# rangkaian_score_foul.net
KiCad netlist of a schematic drawn in EAGLE
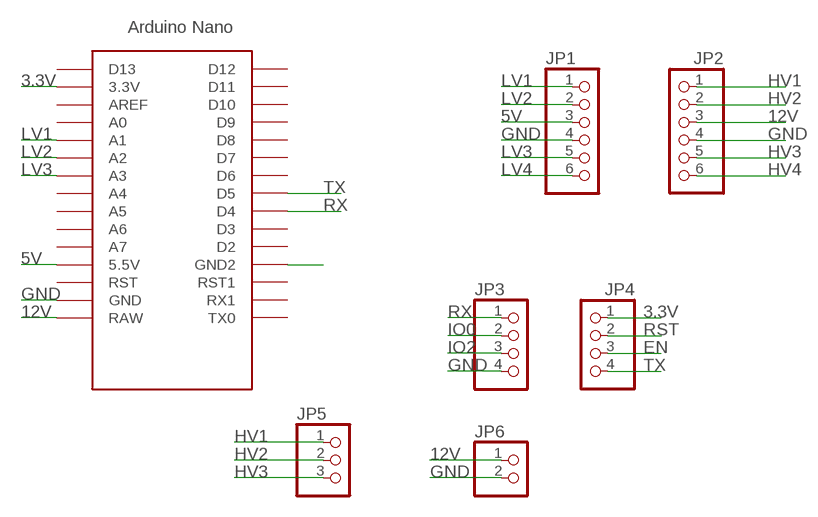
[diagram p0: schematic, sheet 1]

(export (version "E")
  (design (tool "Eeschema 10.0.6"))
  (components
    (comp (ref "JP1")
      (value "PINHD-1X6")
      (footprint "eagle-import:1X06")
      (libsource (lib "eagle-import") (part "PINHD-1X6"))
    )
    (comp (ref "JP2")
      (value "PINHD-1X6")
      (footprint "eagle-import:1X06")
      (libsource (lib "eagle-import") (part "PINHD-1X6"))
    )
    (comp (ref "JP3")
      (value "PINHD-1X4")
      (footprint "eagle-import:1X04")
      (libsource (lib "eagle-import") (part "PINHD-1X4"))
    )
    (comp (ref "JP4")
      (value "PINHD-1X4")
      (footprint "eagle-import:1X04")
      (libsource (lib "eagle-import") (part "PINHD-1X4"))
    )
    (comp (ref "JP5")
      (value "PINHD-1X3")
      (footprint "eagle-import:1X03")
      (libsource (lib "eagle-import") (part "PINHD-1X3"))
    )
    (comp (ref "JP6")
      (value "PINHD-1X2")
      (footprint "eagle-import:1X02")
      (libsource (lib "eagle-import") (part "PINHD-1X2"))
    )
    (comp (ref "U$1")
      (value "NANO")
      (footprint "eagle-import:NANO")
      (libsource (lib "eagle-import") (part "NANO"))
    )
  )
  (nets
    (net (code "1") (name "/3.3V") (class "Default")
      (node (ref "JP4") (pin "1") (pinfunction "1_1") (pintype "passive"))
      (node (ref "U$1") (pin "3.3V") (pinfunction "3.3V_3.3V") (pintype "bidirectional"))
    )
    (net (code "2") (name "/5V") (class "Default")
      (node (ref "JP1") (pin "3") (pinfunction "3_3") (pintype "passive"))
      (node (ref "U$1") (pin "5V") (pinfunction "5.5V_5V") (pintype "bidirectional"))
    )
    (net (code "3") (name "/12V") (class "Default")
      (node (ref "JP2") (pin "3") (pinfunction "3_3") (pintype "passive"))
      (node (ref "JP6") (pin "1") (pinfunction "1_1") (pintype "passive"))
      (node (ref "U$1") (pin "RAW") (pinfunction "RAW_RAW") (pintype "bidirectional"))
    )
    (net (code "4") (name "/EN") (class "Default")
      (node (ref "JP4") (pin "3") (pinfunction "3_3") (pintype "passive"))
    )
    (net (code "5") (name "/GND") (class "Default")
      (node (ref "JP1") (pin "4") (pinfunction "4_4") (pintype "passive"))
      (node (ref "JP2") (pin "4") (pinfunction "4_4") (pintype "passive"))
      (node (ref "JP3") (pin "4") (pinfunction "4_4") (pintype "passive"))
      (node (ref "JP6") (pin "2") (pinfunction "2_2") (pintype "passive"))
      (node (ref "U$1") (pin "GND") (pinfunction "GND_GND") (pintype "bidirectional"))
    )
    (net (code "6") (name "/HV1") (class "Default")
      (node (ref "JP2") (pin "1") (pinfunction "1_1") (pintype "passive"))
      (node (ref "JP5") (pin "1") (pinfunction "1_1") (pintype "passive"))
    )
    (net (code "7") (name "/HV2") (class "Default")
      (node (ref "JP2") (pin "2") (pinfunction "2_2") (pintype "passive"))
      (node (ref "JP5") (pin "2") (pinfunction "2_2") (pintype "passive"))
    )
    (net (code "8") (name "/HV3") (class "Default")
      (node (ref "JP2") (pin "5") (pinfunction "5_5") (pintype "passive"))
      (node (ref "JP5") (pin "3") (pinfunction "3_3") (pintype "passive"))
    )
    (net (code "9") (name "/HV4") (class "Default")
      (node (ref "JP2") (pin "6") (pinfunction "6_6") (pintype "passive"))
    )
    (net (code "10") (name "/IO0") (class "Default")
      (node (ref "JP3") (pin "2") (pinfunction "2_2") (pintype "passive"))
    )
    (net (code "11") (name "/IO2") (class "Default")
      (node (ref "JP3") (pin "3") (pinfunction "3_3") (pintype "passive"))
    )
    (net (code "12") (name "/LV1") (class "Default")
      (node (ref "JP1") (pin "1") (pinfunction "1_1") (pintype "passive"))
      (node (ref "U$1") (pin "A1") (pinfunction "A1_A1") (pintype "bidirectional"))
    )
    (net (code "13") (name "/LV2") (class "Default")
      (node (ref "JP1") (pin "2") (pinfunction "2_2") (pintype "passive"))
      (node (ref "U$1") (pin "A2") (pinfunction "A2_A2") (pintype "bidirectional"))
    )
    (net (code "14") (name "/LV3") (class "Default")
      (node (ref "JP1") (pin "5") (pinfunction "5_5") (pintype "passive"))
      (node (ref "U$1") (pin "A3") (pinfunction "A3_A3") (pintype "bidirectional"))
    )
    (net (code "15") (name "/LV4") (class "Default")
      (node (ref "JP1") (pin "6") (pinfunction "6_6") (pintype "passive"))
    )
    (net (code "16") (name "/RST") (class "Default")
      (node (ref "JP4") (pin "2") (pinfunction "2_2") (pintype "passive"))
    )
    (net (code "17") (name "/RX") (class "Default")
      (node (ref "JP3") (pin "1") (pinfunction "1_1") (pintype "passive"))
      (node (ref "U$1") (pin "D4") (pinfunction "D4_D4") (pintype "bidirectional"))
    )
    (net (code "18") (name "/TX") (class "Default")
      (node (ref "JP4") (pin "4") (pinfunction "4_4") (pintype "passive"))
      (node (ref "U$1") (pin "D5") (pinfunction "D5_D5") (pintype "bidirectional"))
    )
    (net (code "19") (name "unconnected-(U$1-GND2-PadGND1)") (class "Default")
      (node (ref "U$1") (pin "GND1") (pinfunction "GND2_GND1") (pintype "bidirectional"))
    )
    (net (code "20") (name "unconnected-(U$1-PadA0)") (class "Default")
      (node (ref "U$1") (pin "A0") (pinfunction "A0_A0") (pintype "bidirectional"))
    )
    (net (code "21") (name "unconnected-(U$1-PadA4)") (class "Default")
      (node (ref "U$1") (pin "A4") (pinfunction "A4_A4") (pintype "bidirectional"))
    )
    (net (code "22") (name "unconnected-(U$1-PadA5)") (class "Default")
      (node (ref "U$1") (pin "A5") (pinfunction "A5_A5") (pintype "bidirectional"))
    )
    (net (code "23") (name "unconnected-(U$1-PadA6)") (class "Default")
      (node (ref "U$1") (pin "A6") (pinfunction "A6_A6") (pintype "bidirectional"))
    )
    (net (code "24") (name "unconnected-(U$1-PadA7)") (class "Default")
      (node (ref "U$1") (pin "A7") (pinfunction "A7_A7") (pintype "bidirectional"))
    )
    (net (code "25") (name "unconnected-(U$1-PadAREF)") (class "Default")
      (node (ref "U$1") (pin "AREF") (pinfunction "AREF_AREF") (pintype "bidirectional"))
    )
    (net (code "26") (name "unconnected-(U$1-PadD2)") (class "Default")
      (node (ref "U$1") (pin "D2") (pinfunction "D2_D2") (pintype "bidirectional"))
    )
    (net (code "27") (name "unconnected-(U$1-PadD3)") (class "Default")
      (node (ref "U$1") (pin "D3") (pinfunction "D3_D3") (pintype "bidirectional"))
    )
    (net (code "28") (name "unconnected-(U$1-PadD6)") (class "Default")
      (node (ref "U$1") (pin "D6") (pinfunction "D6_D6") (pintype "bidirectional"))
    )
    (net (code "29") (name "unconnected-(U$1-PadD7)") (class "Default")
      (node (ref "U$1") (pin "D7") (pinfunction "D7_D7") (pintype "bidirectional"))
    )
    (net (code "30") (name "unconnected-(U$1-PadD8)") (class "Default")
      (node (ref "U$1") (pin "D8") (pinfunction "D8_D8") (pintype "bidirectional"))
    )
    (net (code "31") (name "unconnected-(U$1-PadD9)") (class "Default")
      (node (ref "U$1") (pin "D9") (pinfunction "D9_D9") (pintype "bidirectional"))
    )
    (net (code "32") (name "unconnected-(U$1-PadD10)") (class "Default")
      (node (ref "U$1") (pin "D10") (pinfunction "D10_D10") (pintype "bidirectional"))
    )
    (net (code "33") (name "unconnected-(U$1-PadD11)") (class "Default")
      (node (ref "U$1") (pin "D11") (pinfunction "D11_D11") (pintype "bidirectional"))
    )
    (net (code "34") (name "unconnected-(U$1-PadD12)") (class "Default")
      (node (ref "U$1") (pin "D12") (pinfunction "D12_D12") (pintype "bidirectional"))
    )
    (net (code "35") (name "unconnected-(U$1-PadD13)") (class "Default")
      (node (ref "U$1") (pin "D13") (pinfunction "D13_D13") (pintype "bidirectional"))
    )
    (net (code "36") (name "unconnected-(U$1-PadICSP1)") (class "Default")
      (node (ref "U$1") (pin "ICSP1") (pinfunction "ICSP1_ICSP1") (pintype "bidirectional"))
    )
    (net (code "37") (name "unconnected-(U$1-PadICSP2)") (class "Default")
      (node (ref "U$1") (pin "ICSP2") (pinfunction "ICSP2_ICSP2") (pintype "bidirectional"))
    )
    (net (code "38") (name "unconnected-(U$1-PadICSP3)") (class "Default")
      (node (ref "U$1") (pin "ICSP3") (pinfunction "ICSP3_ICSP3") (pintype "bidirectional"))
    )
    (net (code "39") (name "unconnected-(U$1-PadICSP4)") (class "Default")
      (node (ref "U$1") (pin "ICSP4") (pinfunction "ICSP4_ICSP4") (pintype "bidirectional"))
    )
    (net (code "40") (name "unconnected-(U$1-PadICSP5)") (class "Default")
      (node (ref "U$1") (pin "ICSP5") (pinfunction "ICSP5_ICSP5") (pintype "bidirectional"))
    )
    (net (code "41") (name "unconnected-(U$1-PadICSP6)") (class "Default")
      (node (ref "U$1") (pin "ICSP6") (pinfunction "ICSP6_ICSP6") (pintype "bidirectional"))
    )
    (net (code "42") (name "unconnected-(U$1-PadRST)") (class "Default")
      (node (ref "U$1") (pin "RST") (pinfunction "RST_RST") (pintype "bidirectional"))
    )
    (net (code "43") (name "unconnected-(U$1-PadRST1)") (class "Default")
      (node (ref "U$1") (pin "RST1") (pinfunction "RST1_RST1") (pintype "bidirectional"))
    )
    (net (code "44") (name "unconnected-(U$1-PadRX1)") (class "Default")
      (node (ref "U$1") (pin "RX1") (pinfunction "RX1_RX1") (pintype "bidirectional"))
    )
    (net (code "45") (name "unconnected-(U$1-PadTX0)") (class "Default")
      (node (ref "U$1") (pin "TX0") (pinfunction "TX0_TX0") (pintype "bidirectional"))
    )
  )
)
